# ClockGen.net
KiCad netlist of a schematic drawn in Altium Designer
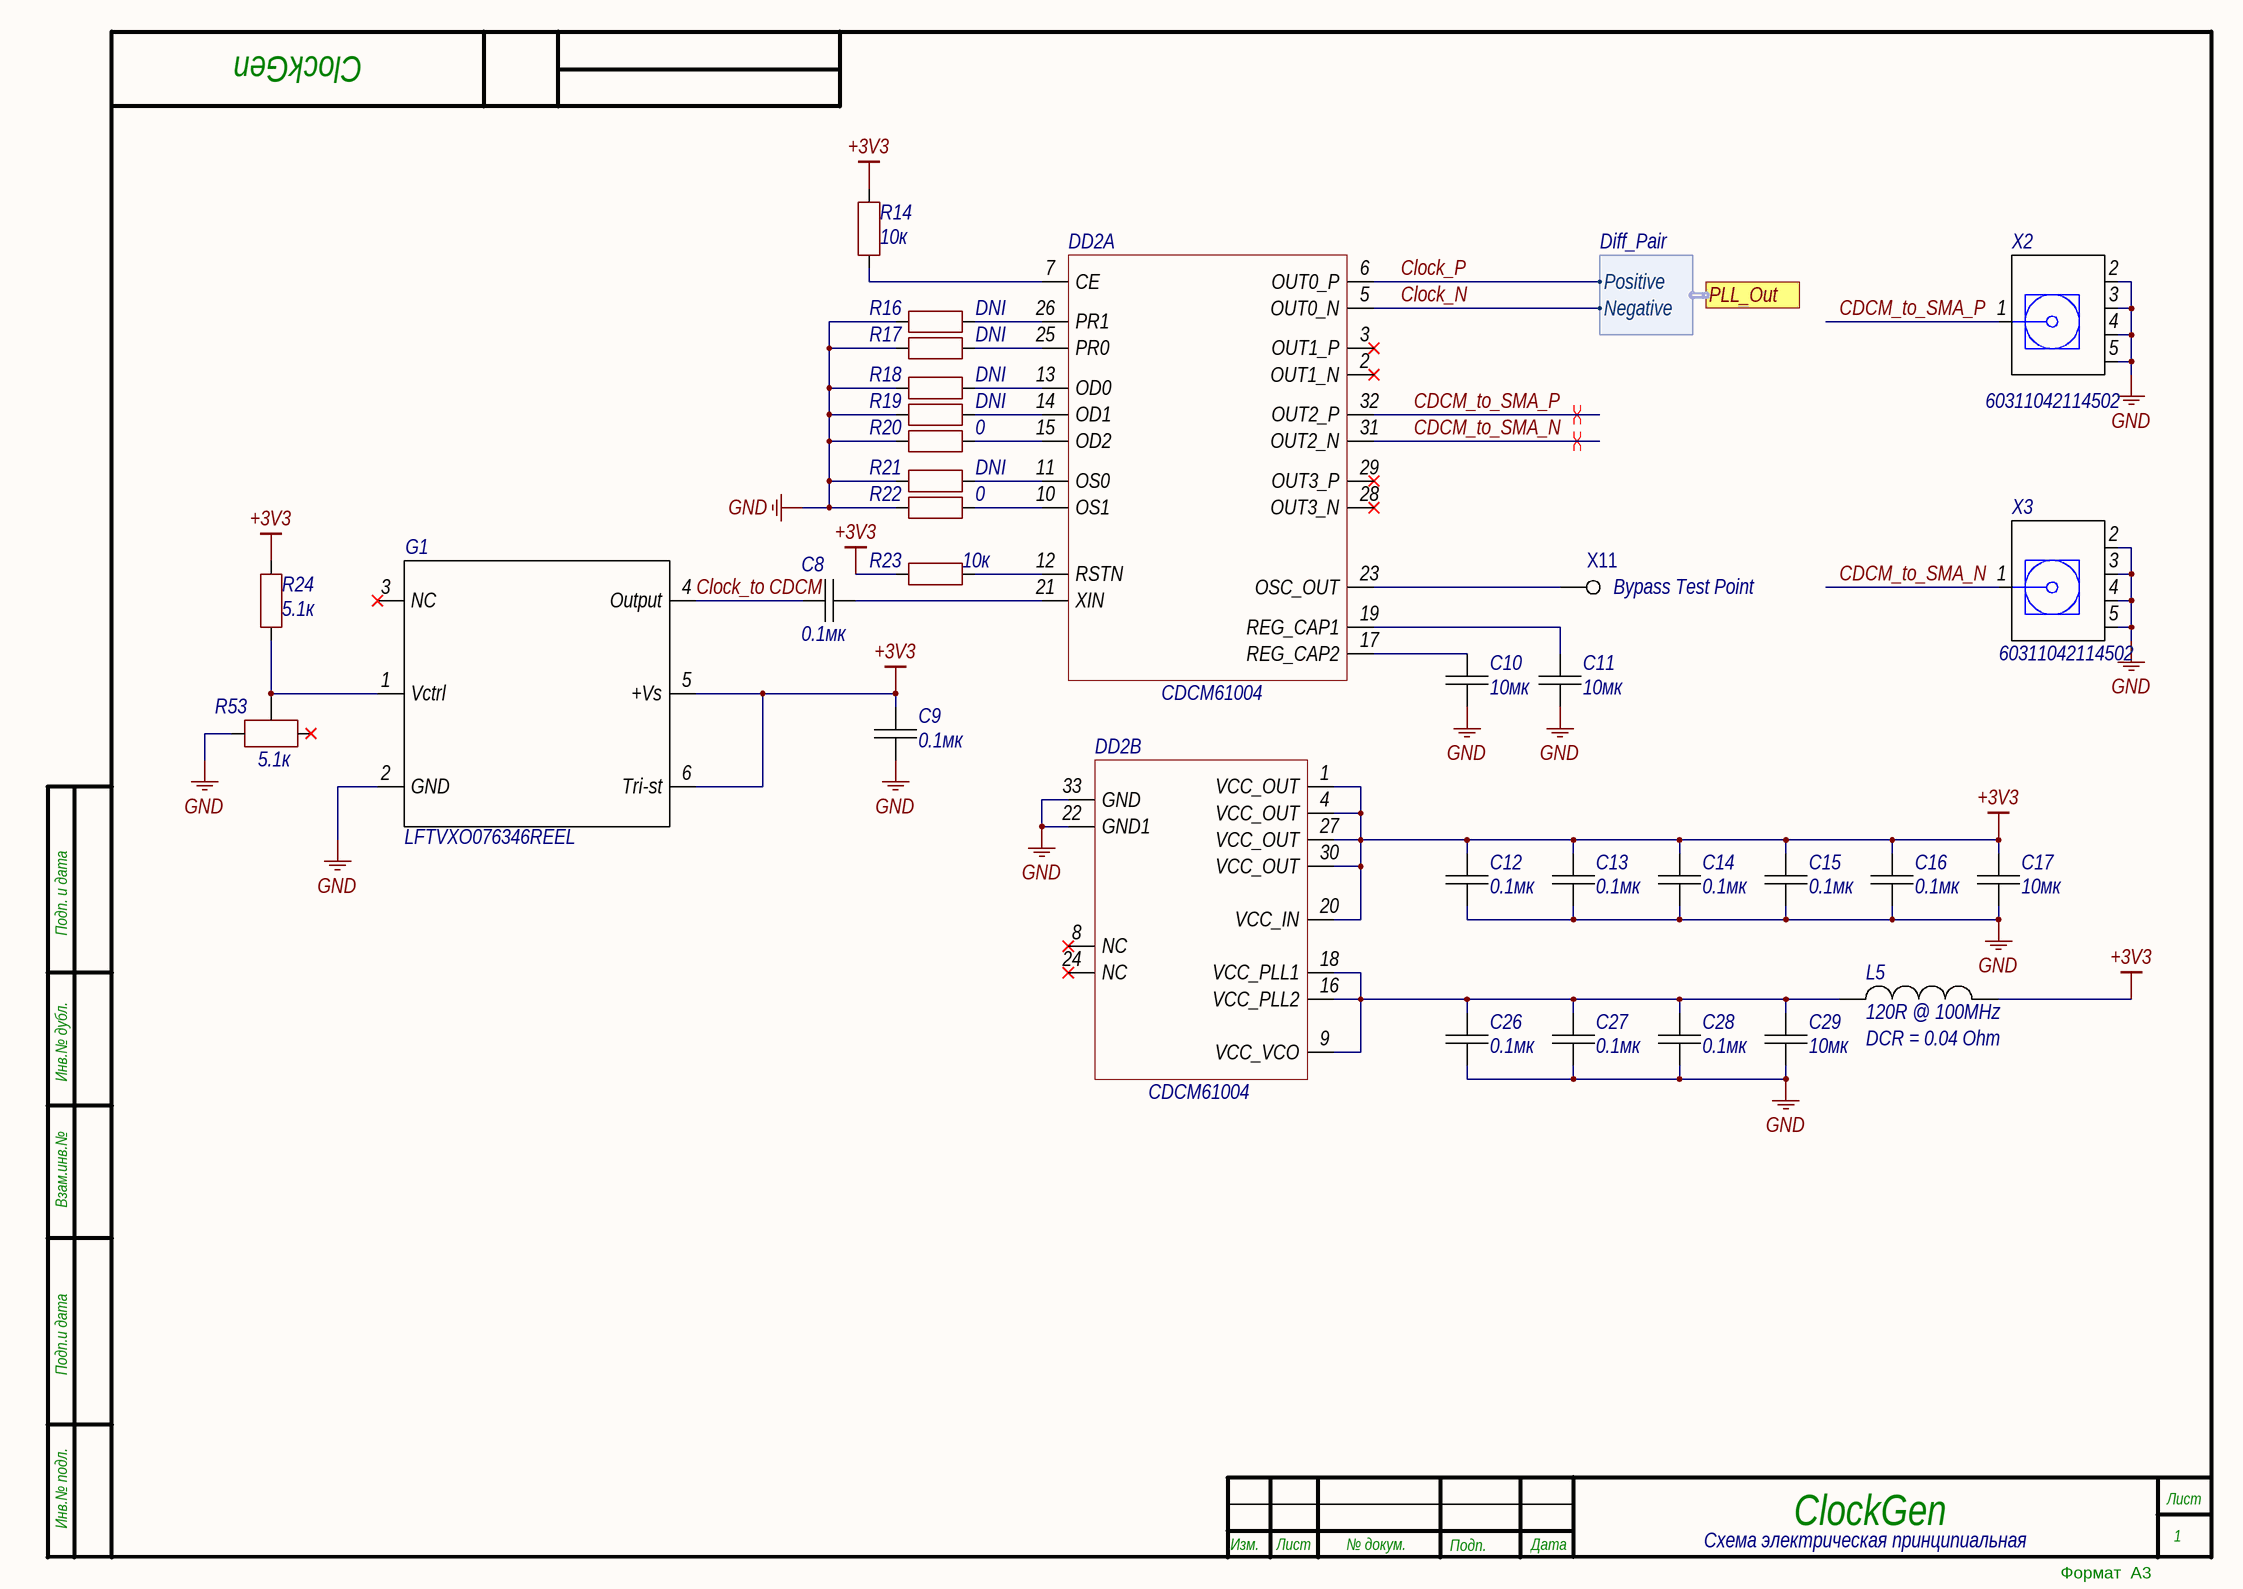
[diagram p0: ClockGen.SchDoc]

(export (version "E")
  (design (tool "Eeschema 10.0.6"))
  (components
    (comp (ref "C8")
      (value "0.1мк")
      (footprint "CAP0402")
      (fields
        (field (name "MANUFACTURER") "Samsung Electro-Mechanics")
        (field (name "MPN") "CL05B104KB54PNC")
        (field (name "TOLERANCE") "10%")
      )
      (libsource (lib "Library") (part "CAPC"))
    )
    (comp (ref "C9")
      (value "0.1мк")
      (footprint "CAPC0805N")
      (fields (field (name "PART NUMBER") "CAPC") (field (name "Comment") "0.1мк *"))
      (libsource (lib "Library") (part "CAPC"))
    )
    (comp (ref "C10")
      (value "10мк")
      (footprint "CAPC0603N")
      (fields
        (field (name "MANUFACTURER") "Samsung Electro-Mechanics")
        (field (name "MPN") "CL10A106KP8NNNC")
        (field (name "TOLERANCE") "10%")
      )
      (libsource (lib "Library") (part "CAPC"))
    )
    (comp (ref "C11")
      (value "10мк")
      (footprint "CAPC0603N")
      (fields
        (field (name "MANUFACTURER") "Samsung Electro-Mechanics")
        (field (name "MPN") "CL10A106KP8NNNC")
        (field (name "TOLERANCE") "10%")
      )
      (libsource (lib "Library") (part "CAPC"))
    )
    (comp (ref "C12")
      (value "0.1мк")
      (footprint "CAP0402")
      (fields
        (field (name "MANUFACTURER") "Samsung Electro-Mechanics")
        (field (name "MPN") "CL05B104KB54PNC")
        (field (name "TOLERANCE") "10%")
      )
      (libsource (lib "Library") (part "CAPC"))
    )
    (comp (ref "C13")
      (value "0.1мк")
      (footprint "CAP0402")
      (fields
        (field (name "MANUFACTURER") "Samsung Electro-Mechanics")
        (field (name "MPN") "CL05B104KB54PNC")
        (field (name "TOLERANCE") "10%")
      )
      (libsource (lib "Library") (part "CAPC"))
    )
    (comp (ref "C14")
      (value "0.1мк")
      (footprint "CAP0402")
      (fields
        (field (name "MANUFACTURER") "Samsung Electro-Mechanics")
        (field (name "MPN") "CL05B104KB54PNC")
        (field (name "TOLERANCE") "10%")
      )
      (libsource (lib "Library") (part "CAPC"))
    )
    (comp (ref "C15")
      (value "0.1мк")
      (footprint "CAP0402")
      (fields
        (field (name "MANUFACTURER") "Samsung Electro-Mechanics")
        (field (name "MPN") "CL05B104KB54PNC")
        (field (name "TOLERANCE") "10%")
      )
      (libsource (lib "Library") (part "CAPC"))
    )
    (comp (ref "C16")
      (value "0.1мк")
      (footprint "CAP0402")
      (fields
        (field (name "MANUFACTURER") "Samsung Electro-Mechanics")
        (field (name "MPN") "CL05B104KB54PNC")
        (field (name "TOLERANCE") "10%")
      )
      (libsource (lib "Library") (part "CAPC"))
    )
    (comp (ref "C17")
      (value "10мк")
      (footprint "CAPC0603N")
      (fields
        (field (name "MANUFACTURER") "Samsung Electro-Mechanics")
        (field (name "MPN") "CL10A106KP8NNNC")
        (field (name "TOLERANCE") "10%")
      )
      (libsource (lib "Library") (part "CAPC"))
    )
    (comp (ref "C26")
      (value "0.1мк")
      (footprint "CAP0402")
      (fields
        (field (name "MANUFACTURER") "Samsung Electro-Mechanics")
        (field (name "MPN") "CL05B104KB54PNC")
        (field (name "TOLERANCE") "10%")
      )
      (libsource (lib "Library") (part "CAPC"))
    )
    (comp (ref "C27")
      (value "0.1мк")
      (footprint "CAP0402")
      (fields
        (field (name "MANUFACTURER") "Samsung Electro-Mechanics")
        (field (name "MPN") "CL05B104KB54PNC")
        (field (name "TOLERANCE") "10%")
      )
      (libsource (lib "Library") (part "CAPC"))
    )
    (comp (ref "C28")
      (value "0.1мк")
      (footprint "CAP0402")
      (fields
        (field (name "MANUFACTURER") "Samsung Electro-Mechanics")
        (field (name "MPN") "CL05B104KB54PNC")
        (field (name "TOLERANCE") "10%")
      )
      (libsource (lib "Library") (part "CAPC"))
    )
    (comp (ref "C29")
      (value "10мк")
      (footprint "CAPC0603N")
      (fields
        (field (name "MANUFACTURER") "Samsung Electro-Mechanics")
        (field (name "MPN") "CL10A106KP8NNNC")
        (field (name "TOLERANCE") "10%")
      )
      (libsource (lib "Library") (part "CAPC"))
    )
    (comp (ref "DD2")
      (value "CDCM61004")
      (footprint "QFN-32_N_TP")
      (fields (field (name "MANUFACTURER") "Texas Instruments"))
      (libsource (lib "Library") (part "CDCM61004"))
    )
    (comp (ref "G1")
      (value "LFTVXO076346REEL")
      (footprint "LFTVXO076346REEL_IQD")
      (fields (field (name "MPN") "LFTVXO076346REEL") (field (name "MANUFACTURER") "IQD"))
      (libsource (lib "Library") (part "LFTVXO076346"))
    )
    (comp (ref "L5")
      (value "DCR = 0.04 Ohm")
      (footprint "IND-0805_N")
      (fields
        (field (name "MANUFACTURER") "Chilisin Elec")
        (field (name "MPN") "PBY201209T-121Y-N")
        (field (name "ALTIUM_VALUE") "120R @ 100MHz")
      )
      (libsource (lib "Library") (part "Inductor"))
    )
    (comp (ref "R14")
      (value "10к")
      (footprint "RESC0402(1005)_M")
      (fields
        (field (name "MANUFACTURER") "UNI-ROYAL(Uniroyal Elec)")
        (field (name "MPN") "0402WGF1002TCE")
        (field (name "PART NUMBER") "RES0402")
      )
      (libsource (lib "") (part "RES_2"))
    )
    (comp (ref "R16")
      (value "DNI")
      (footprint "RESC0402(1005)_M")
      (fields
        (field (name "MANUFACTURER") "UNI-ROYAL(Uniroyal Elec)")
        (field (name "MPN") "0402WGF0000TCE")
        (field (name "PART NUMBER") "RES0402")
      )
      (libsource (lib "Library") (part "RES"))
    )
    (comp (ref "R17")
      (value "DNI")
      (footprint "RESC0402(1005)_M")
      (fields
        (field (name "MANUFACTURER") "UNI-ROYAL(Uniroyal Elec)")
        (field (name "MPN") "0402WGF0000TCE")
        (field (name "PART NUMBER") "RES0402")
      )
      (libsource (lib "Library") (part "RES"))
    )
    (comp (ref "R18")
      (value "DNI")
      (footprint "RESC0402(1005)_M")
      (fields
        (field (name "MANUFACTURER") "UNI-ROYAL(Uniroyal Elec)")
        (field (name "MPN") "0402WGF0000TCE")
        (field (name "PART NUMBER") "RES0402")
      )
      (libsource (lib "Library") (part "RES"))
    )
    (comp (ref "R19")
      (value "DNI")
      (footprint "RESC0402(1005)_M")
      (fields
        (field (name "MANUFACTURER") "UNI-ROYAL(Uniroyal Elec)")
        (field (name "MPN") "0402WGF0000TCE")
        (field (name "PART NUMBER") "RES0402")
      )
      (libsource (lib "Library") (part "RES"))
    )
    (comp (ref "R20")
      (value "0")
      (footprint "RESC0402(1005)_M")
      (fields
        (field (name "MANUFACTURER") "UNI-ROYAL(Uniroyal Elec)")
        (field (name "MPN") "0402WGF0000TCE")
        (field (name "PART NUMBER") "RES0402")
      )
      (libsource (lib "Library") (part "RES"))
    )
    (comp (ref "R21")
      (value "DNI")
      (footprint "RESC0402(1005)_M")
      (fields
        (field (name "MANUFACTURER") "UNI-ROYAL(Uniroyal Elec)")
        (field (name "MPN") "0402WGF0000TCE")
        (field (name "PART NUMBER") "RES0402")
      )
      (libsource (lib "Library") (part "RES"))
    )
    (comp (ref "R22")
      (value "0")
      (footprint "RESC0402(1005)_M")
      (fields
        (field (name "MANUFACTURER") "UNI-ROYAL(Uniroyal Elec)")
        (field (name "MPN") "0402WGF0000TCE")
        (field (name "PART NUMBER") "RES0402")
      )
      (libsource (lib "Library") (part "RES"))
    )
    (comp (ref "R23")
      (value "10к")
      (footprint "RESC0402(1005)_M")
      (fields
        (field (name "MANUFACTURER") "UNI-ROYAL(Uniroyal Elec)")
        (field (name "MPN") "0402WGF1002TCE")
        (field (name "PART NUMBER") "RES0402")
      )
      (libsource (lib "") (part "RES_1"))
    )
    (comp (ref "R24")
      (value "5.1к")
      (footprint "RESC0603N")
      (fields (field (name "PART NUMBER") "RES") (field (name "Comment") "5.1к "))
      (libsource (lib "") (part "RES_2"))
    )
    (comp (ref "R53")
      (value "5.1к")
      (footprint "TRIM_3006P-1-103LF")
      (fields (field (name "PART NUMBER") "TRIM_3006P-1-103LF") (field (name "MANUFACTURER") "Bourns"))
      (libsource (lib "Library") (part "Potenciometr"))
    )
    (comp (ref "X2")
      (value "~")
      (footprint "60311042114502")
      (fields
        (field (name "PART NUMBER") "SMA_WR_60311042114502")
        (field (name "MANUFACTURER") "WE")
        (field (name "MPN") "60311042114502")
      )
      (libsource (lib "Library") (part "SMA_WR_60311042114502"))
    )
    (comp (ref "X3")
      (value "~")
      (footprint "60311042114502")
      (fields
        (field (name "PART NUMBER") "SMA_WR_60311042114502")
        (field (name "MANUFACTURER") "WE")
        (field (name "MPN") "60311042114502")
      )
      (libsource (lib "Library") (part "SMA_WR_60311042114502"))
    )
    (comp (ref "X11")
      (value "PAD-CONNECT-MINI")
      (footprint "PAD-CONNECT-MINI")
      (libsource (lib "Library") (part "PAD-CONNECT-MINI"))
    )
  )
  (nets
    (net (code "2") (name "+3V3") (class "Default")
      (node (ref "C12") (pin "2") (pinfunction "2_2") (pintype "passive"))
      (node (ref "C13") (pin "1") (pinfunction "1_1") (pintype "passive"))
      (node (ref "C14") (pin "1") (pinfunction "1_1") (pintype "passive"))
      (node (ref "C15") (pin "1") (pinfunction "1_1") (pintype "passive"))
      (node (ref "C16") (pin "1") (pinfunction "1_1") (pintype "passive"))
      (node (ref "C17") (pin "2") (pinfunction "2_2") (pintype "passive"))
      (node (ref "C9") (pin "2") (pinfunction "2_2") (pintype "passive"))
      (node (ref "DD2") (pin "1") (pinfunction "VCC_OUT_1") (pintype "passive"))
      (node (ref "DD2") (pin "20") (pinfunction "VCC_IN_20") (pintype "passive"))
      (node (ref "DD2") (pin "27") (pinfunction "VCC_OUT_27") (pintype "passive"))
      (node (ref "DD2") (pin "30") (pinfunction "VCC_OUT_30") (pintype "passive"))
      (node (ref "DD2") (pin "4") (pinfunction "VCC_OUT_4") (pintype "passive"))
      (node (ref "G1") (pin "5") (pinfunction "+Vs_5") (pintype "passive"))
      (node (ref "G1") (pin "6") (pinfunction "Tri-st_6") (pintype "passive"))
      (node (ref "L5") (pin "2") (pinfunction "2_2") (pintype "passive"))
      (node (ref "R14") (pin "2") (pinfunction "2_2") (pintype "passive"))
      (node (ref "R23") (pin "2") (pinfunction "2_2") (pintype "passive"))
      (node (ref "R24") (pin "2") (pinfunction "2_2") (pintype "passive"))
    )
    (net (code "3") (name "/CDCM_to_SMA_N") (class "Default")
      (node (ref "DD2") (pin "31") (pinfunction "OUT2_N_31") (pintype "passive"))
      (node (ref "X3") (pin "1") (pinfunction "Signal_1") (pintype "passive"))
    )
    (net (code "4") (name "/CDCM_to_SMA_P") (class "Default")
      (node (ref "DD2") (pin "32") (pinfunction "OUT2_P_32") (pintype "passive"))
      (node (ref "X2") (pin "1") (pinfunction "Signal_1") (pintype "passive"))
    )
    (net (code "5") (name "/Clock_N") (class "Default")
      (node (ref "DD2") (pin "5") (pinfunction "OUT0_N_5") (pintype "passive"))
    )
    (net (code "6") (name "/Clock_P") (class "Default")
      (node (ref "DD2") (pin "6") (pinfunction "OUT0_P_6") (pintype "passive"))
    )
    (net (code "7") (name "/Clock_to CDCM") (class "Default")
      (node (ref "C8") (pin "1") (pinfunction "1_1") (pintype "passive"))
      (node (ref "G1") (pin "4") (pinfunction "Output_4") (pintype "passive"))
    )
    (net (code "9") (name "GND") (class "Default")
      (node (ref "C10") (pin "1") (pinfunction "1_1") (pintype "passive"))
      (node (ref "C11") (pin "2") (pinfunction "2_2") (pintype "passive"))
      (node (ref "C12") (pin "1") (pinfunction "1_1") (pintype "passive"))
      (node (ref "C13") (pin "2") (pinfunction "2_2") (pintype "passive"))
      (node (ref "C14") (pin "2") (pinfunction "2_2") (pintype "passive"))
      (node (ref "C15") (pin "2") (pinfunction "2_2") (pintype "passive"))
      (node (ref "C16") (pin "2") (pinfunction "2_2") (pintype "passive"))
      (node (ref "C17") (pin "1") (pinfunction "1_1") (pintype "passive"))
      (node (ref "C26") (pin "1") (pinfunction "1_1") (pintype "passive"))
      (node (ref "C27") (pin "2") (pinfunction "2_2") (pintype "passive"))
      (node (ref "C28") (pin "2") (pinfunction "2_2") (pintype "passive"))
      (node (ref "C29") (pin "1") (pinfunction "1_1") (pintype "passive"))
      (node (ref "C9") (pin "1") (pinfunction "1_1") (pintype "passive"))
      (node (ref "DD2") (pin "22") (pinfunction "GND1_22") (pintype "passive"))
      (node (ref "DD2") (pin "33") (pinfunction "GND_33") (pintype "passive"))
      (node (ref "G1") (pin "2") (pinfunction "GND_2") (pintype "passive"))
      (node (ref "R16") (pin "1") (pinfunction "1_1") (pintype "passive"))
      (node (ref "R17") (pin "1") (pinfunction "1_1") (pintype "passive"))
      (node (ref "R18") (pin "1") (pinfunction "1_1") (pintype "passive"))
      (node (ref "R19") (pin "1") (pinfunction "1_1") (pintype "passive"))
      (node (ref "R20") (pin "1") (pinfunction "1_1") (pintype "passive"))
      (node (ref "R21") (pin "1") (pinfunction "1_1") (pintype "passive"))
      (node (ref "R22") (pin "1") (pinfunction "1_1") (pintype "passive"))
      (node (ref "R53") (pin "1") (pinfunction "1_1") (pintype "passive"))
      (node (ref "X2") (pin "2") (pinfunction "GND_2") (pintype "power_in"))
      (node (ref "X2") (pin "3") (pinfunction "GND_3") (pintype "power_in"))
      (node (ref "X2") (pin "4") (pinfunction "GND_4") (pintype "power_in"))
      (node (ref "X2") (pin "5") (pinfunction "GND_5") (pintype "power_in"))
      (node (ref "X3") (pin "2") (pinfunction "GND_2") (pintype "power_in"))
      (node (ref "X3") (pin "3") (pinfunction "GND_3") (pintype "power_in"))
      (node (ref "X3") (pin "4") (pinfunction "GND_4") (pintype "power_in"))
      (node (ref "X3") (pin "5") (pinfunction "GND_5") (pintype "power_in"))
    )
    (net (code "10") (name "Net-(DD2A-CE)") (class "Default")
      (node (ref "DD2") (pin "7") (pinfunction "CE_7") (pintype "passive"))
      (node (ref "R14") (pin "1") (pinfunction "1_1") (pintype "passive"))
    )
    (net (code "11") (name "Net-(DD2A-OD0)") (class "Default")
      (node (ref "DD2") (pin "13") (pinfunction "OD0_13") (pintype "passive"))
      (node (ref "R18") (pin "2") (pinfunction "2_2") (pintype "passive"))
    )
    (net (code "12") (name "Net-(DD2A-OD1)") (class "Default")
      (node (ref "DD2") (pin "14") (pinfunction "OD1_14") (pintype "passive"))
      (node (ref "R19") (pin "2") (pinfunction "2_2") (pintype "passive"))
    )
    (net (code "13") (name "Net-(DD2A-OD2)") (class "Default")
      (node (ref "DD2") (pin "15") (pinfunction "OD2_15") (pintype "passive"))
      (node (ref "R20") (pin "2") (pinfunction "2_2") (pintype "passive"))
    )
    (net (code "14") (name "Net-(DD2A-OS0)") (class "Default")
      (node (ref "DD2") (pin "11") (pinfunction "OS0_11") (pintype "passive"))
      (node (ref "R21") (pin "2") (pinfunction "2_2") (pintype "passive"))
    )
    (net (code "15") (name "Net-(DD2A-OS1)") (class "Default")
      (node (ref "DD2") (pin "10") (pinfunction "OS1_10") (pintype "passive"))
      (node (ref "R22") (pin "2") (pinfunction "2_2") (pintype "passive"))
    )
    (net (code "16") (name "Net-(DD2A-OSC_OUT)") (class "Default")
      (node (ref "DD2") (pin "23") (pinfunction "OSC_OUT_23") (pintype "passive"))
      (node (ref "X11") (pin "1") (pinfunction "1_1") (pintype "passive"))
    )
    (net (code "17") (name "Net-(DD2A-PR0)") (class "Default")
      (node (ref "DD2") (pin "25") (pinfunction "PR0_25") (pintype "passive"))
      (node (ref "R17") (pin "2") (pinfunction "2_2") (pintype "passive"))
    )
    (net (code "18") (name "Net-(DD2A-PR1)") (class "Default")
      (node (ref "DD2") (pin "26") (pinfunction "PR1_26") (pintype "passive"))
      (node (ref "R16") (pin "2") (pinfunction "2_2") (pintype "passive"))
    )
    (net (code "19") (name "Net-(DD2A-REG_CAP1)") (class "Default")
      (node (ref "C11") (pin "1") (pinfunction "1_1") (pintype "passive"))
      (node (ref "DD2") (pin "19") (pinfunction "REG_CAP1_19") (pintype "passive"))
    )
    (net (code "20") (name "Net-(DD2A-REG_CAP2)") (class "Default")
      (node (ref "C10") (pin "2") (pinfunction "2_2") (pintype "passive"))
      (node (ref "DD2") (pin "17") (pinfunction "REG_CAP2_17") (pintype "passive"))
    )
    (net (code "21") (name "Net-(DD2A-RSTN)") (class "Default")
      (node (ref "DD2") (pin "12") (pinfunction "RSTN_12") (pintype "passive"))
      (node (ref "R23") (pin "1") (pinfunction "1_1") (pintype "passive"))
    )
    (net (code "22") (name "Net-(DD2A-XIN)") (class "Default")
      (node (ref "C8") (pin "2") (pinfunction "2_2") (pintype "passive"))
      (node (ref "DD2") (pin "21") (pinfunction "XIN_21") (pintype "passive"))
    )
    (net (code "23") (name "Net-(DD2B-VCC_PLL1)") (class "Default")
      (node (ref "C26") (pin "2") (pinfunction "2_2") (pintype "passive"))
      (node (ref "C27") (pin "1") (pinfunction "1_1") (pintype "passive"))
      (node (ref "C28") (pin "1") (pinfunction "1_1") (pintype "passive"))
      (node (ref "C29") (pin "2") (pinfunction "2_2") (pintype "passive"))
      (node (ref "DD2") (pin "16") (pinfunction "VCC_PLL2_16") (pintype "passive"))
      (node (ref "DD2") (pin "18") (pinfunction "VCC_PLL1_18") (pintype "passive"))
      (node (ref "DD2") (pin "9") (pinfunction "VCC_VCO_9") (pintype "passive"))
      (node (ref "L5") (pin "1") (pinfunction "1_1") (pintype "passive"))
    )
    (net (code "24") (name "Net-(G1-Vctrl)") (class "Default")
      (node (ref "G1") (pin "1") (pinfunction "Vctrl_1") (pintype "passive"))
      (node (ref "R24") (pin "1") (pinfunction "1_1") (pintype "passive"))
      (node (ref "R53") (pin "2") (pinfunction "2_2") (pintype "passive"))
    )
    (net (code "25") (name "unconnected-(DD2A-OUT1_N-Pad2)") (class "Default")
      (node (ref "DD2") (pin "2") (pinfunction "OUT1_N_2") (pintype "passive+no_connect"))
    )
    (net (code "26") (name "unconnected-(DD2A-OUT1_P-Pad3)") (class "Default")
      (node (ref "DD2") (pin "3") (pinfunction "OUT1_P_3") (pintype "passive+no_connect"))
    )
    (net (code "27") (name "unconnected-(DD2A-OUT3_N-Pad28)") (class "Default")
      (node (ref "DD2") (pin "28") (pinfunction "OUT3_N_28") (pintype "passive+no_connect"))
    )
    (net (code "28") (name "unconnected-(DD2A-OUT3_P-Pad29)") (class "Default")
      (node (ref "DD2") (pin "29") (pinfunction "OUT3_P_29") (pintype "passive+no_connect"))
    )
    (net (code "29") (name "unconnected-(DD2B-NC-Pad8)") (class "Default")
      (node (ref "DD2") (pin "8") (pinfunction "NC_8") (pintype "passive+no_connect"))
    )
    (net (code "30") (name "unconnected-(DD2B-NC-Pad24)") (class "Default")
      (node (ref "DD2") (pin "24") (pinfunction "NC_24") (pintype "passive+no_connect"))
    )
    (net (code "31") (name "unconnected-(G1-NC-Pad3)") (class "Default")
      (node (ref "G1") (pin "3") (pinfunction "NC_3") (pintype "passive+no_connect"))
    )
    (net (code "32") (name "unconnected-(R53-Pad3)") (class "Default")
      (node (ref "R53") (pin "3") (pinfunction "3_3") (pintype "passive+no_connect"))
    )
  )
)
